# 09_SDIO_PERIPHERAL.net
KiCad netlist of a schematic drawn in Altium Designer
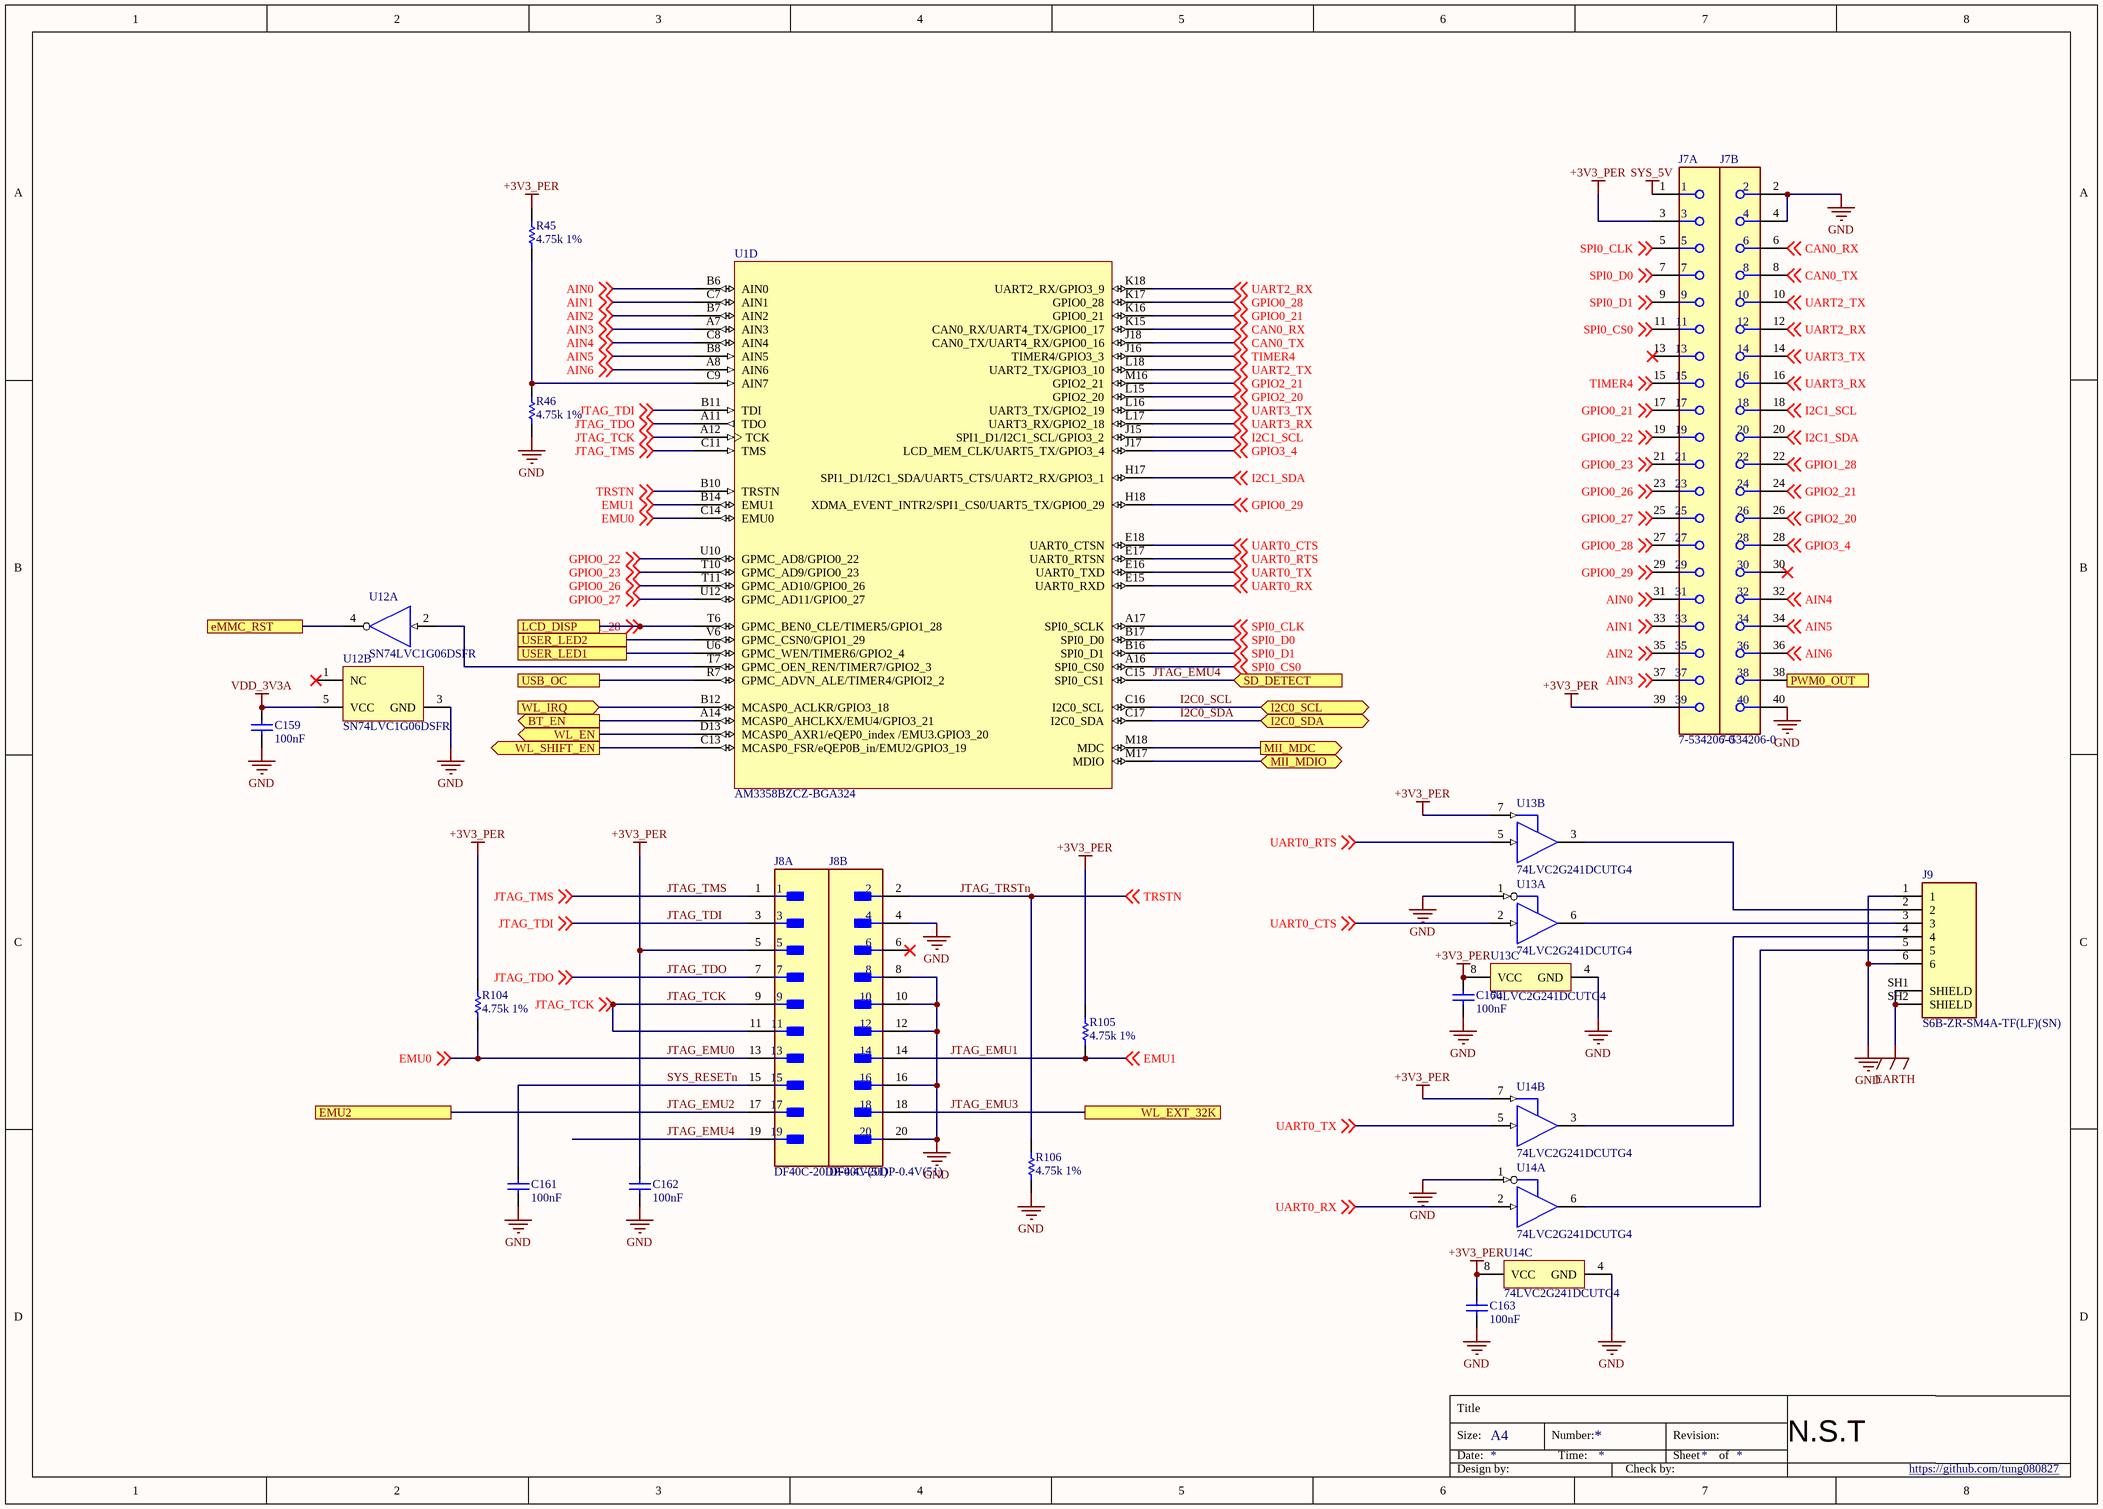
[diagram p0: 09. SDIO, PERIPHERAL.SchDoc]

(export (version "E")
  (design (tool "Eeschema 10.0.6"))
  (components
    (comp (ref "C159")
      (value "100nF")
      (footprint "CAPC1005X55X25LL05T10")
      (description "Chip Capacitor, 0.1 uF, +/- 10%, 16 V, -55 to 125 degC, 0402 (1005 Metric), RoHS, Tape and Reel")
      (fields (field (name "VOLTAGE") "16V") (field (name "TOLERANCE") "10%"))
      (libsource (lib "Altium Content Vault") (part "CAP-NP-2"))
    )
    (comp (ref "C160")
      (value "100nF")
      (footprint "CAPC1005X55X25LL05T10")
      (description "Chip Capacitor, 0.1 uF, +/- 10%, 16 V, -55 to 125 degC, 0402 (1005 Metric), RoHS, Tape and Reel")
      (fields (field (name "VOLTAGE") "16V") (field (name "TOLERANCE") "10%"))
      (libsource (lib "Altium Content Vault") (part "CAP-NP-2"))
    )
    (comp (ref "C161")
      (value "100nF")
      (footprint "CAPC1005X55X25LL05T10")
      (description "Chip Capacitor, 0.1 uF, +/- 10%, 16 V, -55 to 125 degC, 0402 (1005 Metric), RoHS, Tape and Reel")
      (fields (field (name "VOLTAGE") "16V") (field (name "TOLERANCE") "10%"))
      (libsource (lib "Altium Content Vault") (part "CAP-NP-2"))
    )
    (comp (ref "C162")
      (value "100nF")
      (footprint "CAPC1005X55X25LL05T10")
      (description "Chip Capacitor, 0.1 uF, +/- 10%, 16 V, -55 to 125 degC, 0402 (1005 Metric), RoHS, Tape and Reel")
      (fields (field (name "VOLTAGE") "16V") (field (name "TOLERANCE") "10%"))
      (libsource (lib "Altium Content Vault") (part "CAP-NP-2"))
    )
    (comp (ref "C163")
      (value "100nF")
      (footprint "CAPC1005X55X25LL05T10")
      (description "Chip Capacitor, 0.1 uF, +/- 10%, 16 V, -55 to 125 degC, 0402 (1005 Metric), RoHS, Tape and Reel")
      (fields (field (name "VOLTAGE") "16V") (field (name "TOLERANCE") "10%"))
      (libsource (lib "Altium Content Vault") (part "CAP-NP-2"))
    )
    (comp (ref "J7")
      (value "7-534206-0")
      (footprint "FP-7-534206-0-MFG")
      (description "CONN RCPT 40POS 0.1 GOLD PCB")
      (fields
        (field (name "MANUFACTURER") "TE Connectivity")
        (field (name "OCTOPART") "https://octopart.com/7-534206-0-te+connectivity-39516831")
      )
      (libsource (lib "Altium Content Vault") (part "7acf1c4a8db21028d11741a46a6ec78"))
    )
    (comp (ref "J8")
      (value "DF40C-20DP-0.4V(51)")
      (footprint "FP-DF40C-20DP-0_4V_51-MFG")
      (description "CONN PLUG 20POS SMD GOLD")
      (fields
        (field (name "MANUFACTURER") "Hirose")
        (field (name "OCTOPART") "https://octopart.com/df40c-20dp-0.4v%2851%29-hirose-11540400")
      )
      (libsource (lib "Altium Content Vault") (part "6de6f85b73b81876561c0123e7b9d68"))
    )
    (comp (ref "J9")
      (value "S6B-ZR-SM4A-TF(LF)(SN)")
      (footprint "JST_S6B-ZR-SM4A-TF")
      (description "Connector Header Surface Mount, Right Angle 6 position 0.059 _1.50mm_")
      (fields
        (field (name "MP") "S6B-ZR-SM4A-TF_LF__SN_")
        (field (name "DIGI-KEY_PART_NUMBER") "455-1610-1-ND")
      )
      (libsource (lib "SyTungNguyen") (part "S6B-ZR-SM4A-TF(LF)(SN)"))
    )
    (comp (ref "R45")
      (value "4.75k 1%")
      (footprint "RESC1005X40X25LL05T05")
      (fields (field (name "MANUFACTURER") "Vishay Dale") (field (name "PART NUMBER") "CRCW04024K75FKED"))
      (libsource (lib "AM3358_DEV_BOARD") (part "RES"))
    )
    (comp (ref "R46")
      (value "4.75k 1%")
      (footprint "RESC1005X40X25LL05T05")
      (fields (field (name "MANUFACTURER") "Vishay Dale") (field (name "PART NUMBER") "CRCW04024K75FKED"))
      (libsource (lib "AM3358_DEV_BOARD") (part "RES"))
    )
    (comp (ref "R104")
      (value "4.75k 1%")
      (footprint "RESC1005X40X25LL05T05")
      (fields (field (name "MANUFACTURER") "Vishay Dale") (field (name "PART NUMBER") "CRCW04024K75FKED"))
      (libsource (lib "AM3358_DEV_BOARD") (part "RES"))
    )
    (comp (ref "R105")
      (value "4.75k 1%")
      (footprint "RESC1005X40X25LL05T05")
      (fields (field (name "MANUFACTURER") "Vishay Dale") (field (name "PART NUMBER") "CRCW04024K75FKED"))
      (libsource (lib "AM3358_DEV_BOARD") (part "RES"))
    )
    (comp (ref "R106")
      (value "4.75k 1%")
      (footprint "RESC1005X40X25LL05T05")
      (fields (field (name "MANUFACTURER") "Vishay Dale") (field (name "PART NUMBER") "CRCW04024K75FKED"))
      (libsource (lib "AM3358_DEV_BOARD") (part "RES"))
    )
    (comp (ref "U1")
      (value "AM3358BZCZ-BGA324")
      (footprint "TI-ZCZ324")
      (libsource (lib "SyTungNguyen") (part "AM3358BZCZ100"))
    )
    (comp (ref "U12")
      (value "SN74LVC1G06DSFR")
      (footprint "DSF0006A_V")
      (description "Single Inverter Buffer/Driver With Open-Drain Output, DSF0006A, LARGE T&R")
      (fields
        (field (name "MANUFACTURER") "Texas Instruments")
        (field (name "GENERIC PART NUMBER") "SN74LVC1G06")
      )
      (libsource (lib "") (part "TI-SN74XXX1G06-5_1"))
    )
    (comp (ref "U13")
      (value "74LVC2G241DCUTG4")
      (footprint "DCU0008A_M")
      (description "Dual Buffer/Driver With 3-State Outputs, DCU0008A, SMALL T&R")
      (fields
        (field (name "MANUFACTURER") "Texas Instruments")
        (field (name "GENERIC PART NUMBER") "SN74LVC2G241")
      )
      (libsource (lib "Altium Content Vault") (part "TI-SN74XXX2G241-8"))
    )
    (comp (ref "U14")
      (value "74LVC2G241DCUTG4")
      (footprint "DCU0008A_M")
      (description "Dual Buffer/Driver With 3-State Outputs, DCU0008A, SMALL T&R")
      (fields
        (field (name "MANUFACTURER") "Texas Instruments")
        (field (name "GENERIC PART NUMBER") "SN74LVC2G241")
      )
      (libsource (lib "Altium Content Vault") (part "TI-SN74XXX2G241-8"))
    )
  )
  (nets
    (net (code "1") (name "+3V3_PER") (class "Default")
      (node (ref "C160") (pin "2") (pinfunction "2_2") (pintype "passive"))
      (node (ref "C162") (pin "2") (pinfunction "2_2") (pintype "passive"))
      (node (ref "C163") (pin "2") (pinfunction "2_2") (pintype "passive"))
      (node (ref "J7") (pin "3") (pinfunction "3_3") (pintype "passive"))
      (node (ref "J7") (pin "39") (pinfunction "39_39") (pintype "passive"))
      (node (ref "J8") (pin "5") (pinfunction "5_5") (pintype "passive"))
      (node (ref "R104") (pin "2") (pinfunction "2_2") (pintype "passive"))
      (node (ref "R105") (pin "2") (pinfunction "2_2") (pintype "passive"))
      (node (ref "R45") (pin "2") (pinfunction "2_2") (pintype "passive"))
      (node (ref "U13") (pin "7") (pinfunction "2OE_7") (pintype "input"))
      (node (ref "U13") (pin "8") (pinfunction "VCC_8") (pintype "power_in"))
      (node (ref "U14") (pin "7") (pinfunction "2OE_7") (pintype "input"))
      (node (ref "U14") (pin "8") (pinfunction "VCC_8") (pintype "power_in"))
    )
    (net (code "2") (name "/BT_EN") (class "Default")
      (node (ref "U1") (pin "A14") (pinfunction "MCASP0_AHCLKX/EMU4/GPIO3_21_A14") (pintype "bidirectional"))
    )
    (net (code "3") (name "/I2C0_SCL") (class "Default")
      (node (ref "U1") (pin "C16") (pinfunction "I2C0_SCL_C16") (pintype "bidirectional"))
    )
    (net (code "4") (name "/I2C0_SDA") (class "Default")
      (node (ref "U1") (pin "C17") (pinfunction "I2C0_SDA_C17") (pintype "bidirectional"))
    )
    (net (code "5") (name "/JTAG_EMU2") (class "Default")
      (node (ref "J8") (pin "17") (pinfunction "17_17") (pintype "passive"))
    )
    (net (code "6") (name "/JTAG_EMU3") (class "Default")
      (node (ref "J8") (pin "18") (pinfunction "18_18") (pintype "passive"))
    )
    (net (code "7") (name "/JTAG_EMU4") (class "Default")
      (node (ref "J8") (pin "19") (pinfunction "19_19") (pintype "passive"))
      (node (ref "U1") (pin "C15") (pinfunction "SPI0_CS1_C15") (pintype "bidirectional"))
    )
    (net (code "8") (name "/MII_MDC") (class "Default")
      (node (ref "U1") (pin "M18") (pinfunction "MDC_M18") (pintype "bidirectional"))
    )
    (net (code "9") (name "/MII_MDIO") (class "Default")
      (node (ref "U1") (pin "M17") (pinfunction "MDIO_M17") (pintype "bidirectional"))
    )
    (net (code "10") (name "/PWM0_OUT") (class "Default")
      (node (ref "J7") (pin "38") (pinfunction "38_38") (pintype "passive"))
    )
    (net (code "11") (name "/SYS_RESETn") (class "Default")
      (node (ref "C161") (pin "2") (pinfunction "2_2") (pintype "passive"))
      (node (ref "J8") (pin "15") (pinfunction "15_15") (pintype "passive"))
    )
    (net (code "12") (name "/USB_OC") (class "Default")
      (node (ref "U1") (pin "R7") (pinfunction "GPMC_ADVN_ALE/TIMER4/GPIOI2_2_R7") (pintype "bidirectional"))
    )
    (net (code "13") (name "/USER_LED1") (class "Default")
      (node (ref "U1") (pin "U6") (pinfunction "GPMC_WEN/TIMER6/GPIO2_4_U6") (pintype "bidirectional"))
    )
    (net (code "14") (name "/USER_LED2") (class "Default")
      (node (ref "U1") (pin "V6") (pinfunction "GPMC_CSN0/GPIO1_29_V6") (pintype "bidirectional"))
    )
    (net (code "15") (name "/WL_EN") (class "Default")
      (node (ref "U1") (pin "D13") (pinfunction "MCASP0_AXR1/eQEP0_index_/EMU3.GPIO3_20_D13") (pintype "bidirectional"))
    )
    (net (code "16") (name "/WL_IRQ") (class "Default")
      (node (ref "U1") (pin "B12") (pinfunction "MCASP0_ACLKR/GPIO3_18_B12") (pintype "bidirectional"))
    )
    (net (code "17") (name "/WL_SHIFT_EN") (class "Default")
      (node (ref "U1") (pin "C13") (pinfunction "MCASP0_FSR/eQEP0B_in/EMU2/GPIO3_19_C13") (pintype "bidirectional"))
    )
    (net (code "18") (name "/eMMC_RST") (class "Default")
      (node (ref "U12") (pin "4") (pinfunction "Y_4") (pintype "open_collector"))
    )
    (net (code "19") (name "AIN0") (class "Default")
      (node (ref "J7") (pin "31") (pinfunction "31_31") (pintype "passive"))
      (node (ref "U1") (pin "B6") (pinfunction "AIN0_B6") (pintype "bidirectional"))
    )
    (net (code "20") (name "AIN1") (class "Default")
      (node (ref "J7") (pin "33") (pinfunction "33_33") (pintype "passive"))
      (node (ref "U1") (pin "C7") (pinfunction "AIN1_C7") (pintype "bidirectional"))
    )
    (net (code "21") (name "AIN2") (class "Default")
      (node (ref "J7") (pin "35") (pinfunction "35_35") (pintype "passive"))
      (node (ref "U1") (pin "B7") (pinfunction "AIN2_B7") (pintype "bidirectional"))
    )
    (net (code "22") (name "AIN3") (class "Default")
      (node (ref "J7") (pin "37") (pinfunction "37_37") (pintype "passive"))
      (node (ref "U1") (pin "A7") (pinfunction "AIN3_A7") (pintype "bidirectional"))
    )
    (net (code "23") (name "AIN4") (class "Default")
      (node (ref "J7") (pin "32") (pinfunction "32_32") (pintype "passive"))
      (node (ref "U1") (pin "C8") (pinfunction "AIN4_C8") (pintype "bidirectional"))
    )
    (net (code "24") (name "AIN5") (class "Default")
      (node (ref "J7") (pin "34") (pinfunction "34_34") (pintype "passive"))
      (node (ref "U1") (pin "B8") (pinfunction "AIN5_B8") (pintype "input"))
    )
    (net (code "25") (name "AIN6") (class "Default")
      (node (ref "J7") (pin "36") (pinfunction "36_36") (pintype "passive"))
      (node (ref "U1") (pin "A8") (pinfunction "AIN6_A8") (pintype "input"))
    )
    (net (code "26") (name "CAN0_RX") (class "Default")
      (node (ref "J7") (pin "6") (pinfunction "6_6") (pintype "passive"))
      (node (ref "U1") (pin "K15") (pinfunction "CAN0_RX/UART4_TX/GPIO0_17_K15") (pintype "bidirectional"))
    )
    (net (code "27") (name "CAN0_TX") (class "Default")
      (node (ref "J7") (pin "8") (pinfunction "8_8") (pintype "passive"))
      (node (ref "U1") (pin "J18") (pinfunction "CAN0_TX/UART4_RX/GPIO0_16_J18") (pintype "bidirectional"))
    )
    (net (code "28") (name "EARTH") (class "Default")
      (node (ref "J9") (pin "SH1") (pinfunction "SHIELD_SH1") (pintype "passive"))
      (node (ref "J9") (pin "SH2") (pinfunction "SHIELD_SH2") (pintype "passive"))
    )
    (net (code "29") (name "EMU0") (class "Default")
      (node (ref "J8") (pin "13") (pinfunction "13_13") (pintype "passive"))
      (node (ref "R104") (pin "1") (pinfunction "1_1") (pintype "passive"))
      (node (ref "U1") (pin "C14") (pinfunction "EMU0_C14") (pintype "bidirectional"))
    )
    (net (code "30") (name "EMU1") (class "Default")
      (node (ref "J8") (pin "14") (pinfunction "14_14") (pintype "passive"))
      (node (ref "R105") (pin "1") (pinfunction "1_1") (pintype "passive"))
      (node (ref "U1") (pin "B14") (pinfunction "EMU1_B14") (pintype "bidirectional"))
    )
    (net (code "31") (name "GND") (class "Default")
      (node (ref "C159") (pin "1") (pinfunction "1_1") (pintype "passive"))
      (node (ref "C160") (pin "1") (pinfunction "1_1") (pintype "passive"))
      (node (ref "C161") (pin "1") (pinfunction "1_1") (pintype "passive"))
      (node (ref "C162") (pin "1") (pinfunction "1_1") (pintype "passive"))
      (node (ref "C163") (pin "1") (pinfunction "1_1") (pintype "passive"))
      (node (ref "J7") (pin "2") (pinfunction "2_2") (pintype "passive"))
      (node (ref "J7") (pin "4") (pinfunction "4_4") (pintype "passive"))
      (node (ref "J7") (pin "40") (pinfunction "40_40") (pintype "passive"))
      (node (ref "J8") (pin "10") (pinfunction "10_10") (pintype "passive"))
      (node (ref "J8") (pin "12") (pinfunction "12_12") (pintype "passive"))
      (node (ref "J8") (pin "16") (pinfunction "16_16") (pintype "passive"))
      (node (ref "J8") (pin "20") (pinfunction "20_20") (pintype "passive"))
      (node (ref "J8") (pin "4") (pinfunction "4_4") (pintype "passive"))
      (node (ref "J8") (pin "8") (pinfunction "8_8") (pintype "passive"))
      (node (ref "J9") (pin "1") (pinfunction "1_1") (pintype "passive"))
      (node (ref "J9") (pin "6") (pinfunction "6_6") (pintype "passive"))
      (node (ref "R106") (pin "1") (pinfunction "1_1") (pintype "passive"))
      (node (ref "R46") (pin "1") (pinfunction "1_1") (pintype "passive"))
      (node (ref "U12") (pin "3") (pinfunction "GND_3") (pintype "power_in"))
      (node (ref "U13") (pin "1") (pinfunction "1~{OE}_1") (pintype "input"))
      (node (ref "U13") (pin "4") (pinfunction "GND_4") (pintype "power_in"))
      (node (ref "U14") (pin "1") (pinfunction "1~{OE}_1") (pintype "input"))
      (node (ref "U14") (pin "4") (pinfunction "GND_4") (pintype "power_in"))
    )
    (net (code "32") (name "GPIO0_21") (class "Default")
      (node (ref "J7") (pin "17") (pinfunction "17_17") (pintype "passive"))
      (node (ref "U1") (pin "K16") (pinfunction "GPIO0_21_K16") (pintype "bidirectional"))
    )
    (net (code "33") (name "GPIO0_22") (class "Default")
      (node (ref "J7") (pin "19") (pinfunction "19_19") (pintype "passive"))
      (node (ref "U1") (pin "U10") (pinfunction "GPMC_AD8/GPIO0_22_U10") (pintype "bidirectional"))
    )
    (net (code "34") (name "GPIO0_23") (class "Default")
      (node (ref "J7") (pin "21") (pinfunction "21_21") (pintype "passive"))
      (node (ref "U1") (pin "T10") (pinfunction "GPMC_AD9/GPIO0_23_T10") (pintype "bidirectional"))
    )
    (net (code "35") (name "GPIO0_26") (class "Default")
      (node (ref "J7") (pin "23") (pinfunction "23_23") (pintype "passive"))
      (node (ref "U1") (pin "T11") (pinfunction "GPMC_AD10/GPIO0_26_T11") (pintype "bidirectional"))
    )
    (net (code "36") (name "GPIO0_27") (class "Default")
      (node (ref "J7") (pin "25") (pinfunction "25_25") (pintype "passive"))
      (node (ref "U1") (pin "U12") (pinfunction "GPMC_AD11/GPIO0_27_U12") (pintype "bidirectional"))
    )
    (net (code "37") (name "GPIO0_28") (class "Default")
      (node (ref "J7") (pin "27") (pinfunction "27_27") (pintype "passive"))
      (node (ref "U1") (pin "K17") (pinfunction "GPIO0_28_K17") (pintype "bidirectional"))
    )
    (net (code "38") (name "GPIO0_29") (class "Default")
      (node (ref "J7") (pin "29") (pinfunction "29_29") (pintype "passive"))
      (node (ref "U1") (pin "H18") (pinfunction "XDMA_EVENT_INTR2/SPI1_CS0/UART5_TX/GPIO0_29_H18") (pintype "bidirectional"))
    )
    (net (code "39") (name "GPIO1_28") (class "Default")
      (node (ref "J7") (pin "22") (pinfunction "22_22") (pintype "passive"))
      (node (ref "U1") (pin "T6") (pinfunction "GPMC_BEN0_CLE/TIMER5/GPIO1_28_T6") (pintype "bidirectional"))
    )
    (net (code "40") (name "GPIO2_20") (class "Default")
      (node (ref "J7") (pin "26") (pinfunction "26_26") (pintype "passive"))
      (node (ref "U1") (pin "L15") (pinfunction "GPIO2_20_L15") (pintype "bidirectional"))
    )
    (net (code "41") (name "GPIO2_21") (class "Default")
      (node (ref "J7") (pin "24") (pinfunction "24_24") (pintype "passive"))
      (node (ref "U1") (pin "M16") (pinfunction "GPIO2_21_M16") (pintype "bidirectional"))
    )
    (net (code "42") (name "GPIO3_4") (class "Default")
      (node (ref "J7") (pin "28") (pinfunction "28_28") (pintype "passive"))
      (node (ref "U1") (pin "J17") (pinfunction "LCD_MEM_CLK/UART5_TX/GPIO3_4_J17") (pintype "bidirectional"))
    )
    (net (code "43") (name "I2C1_SCL") (class "Default")
      (node (ref "J7") (pin "18") (pinfunction "18_18") (pintype "passive"))
      (node (ref "U1") (pin "J15") (pinfunction "SPI1_D1/I2C1_SCL/GPIO3_2_J15") (pintype "bidirectional"))
    )
    (net (code "44") (name "I2C1_SDA") (class "Default")
      (node (ref "J7") (pin "20") (pinfunction "20_20") (pintype "passive"))
      (node (ref "U1") (pin "H17") (pinfunction "SPI1_D1/I2C1_SDA/UART5_CTS/UART2_RX/GPIO3_1_H17") (pintype "bidirectional"))
    )
    (net (code "45") (name "JTAG_TCK") (class "Default")
      (node (ref "J8") (pin "11") (pinfunction "11_11") (pintype "passive"))
      (node (ref "J8") (pin "9") (pinfunction "9_9") (pintype "passive"))
      (node (ref "U1") (pin "A12") (pinfunction "TCK_A12") (pintype "input"))
    )
    (net (code "46") (name "JTAG_TDI") (class "Default")
      (node (ref "J8") (pin "3") (pinfunction "3_3") (pintype "passive"))
      (node (ref "U1") (pin "B11") (pinfunction "TDI_B11") (pintype "input"))
    )
    (net (code "47") (name "JTAG_TDO") (class "Default")
      (node (ref "J8") (pin "7") (pinfunction "7_7") (pintype "passive"))
      (node (ref "U1") (pin "A11") (pinfunction "TDO_A11") (pintype "output"))
    )
    (net (code "48") (name "JTAG_TMS") (class "Default")
      (node (ref "J8") (pin "1") (pinfunction "1_1") (pintype "passive"))
      (node (ref "U1") (pin "C11") (pinfunction "TMS_C11") (pintype "input"))
    )
    (net (code "49") (name "Net-(U1D-AIN7)") (class "Default")
      (node (ref "R45") (pin "1") (pinfunction "1_1") (pintype "passive"))
      (node (ref "R46") (pin "2") (pinfunction "2_2") (pintype "passive"))
      (node (ref "U1") (pin "C9") (pinfunction "AIN7_C9") (pintype "input"))
    )
    (net (code "50") (name "Net-(U12A-A)") (class "Default")
      (node (ref "U1") (pin "T7") (pinfunction "GPMC_OEN_REN/TIMER7/GPIO2_3_T7") (pintype "bidirectional"))
      (node (ref "U12") (pin "2") (pinfunction "A_2") (pintype "input"))
    )
    (net (code "51") (name "Net-(U13A-1Y)") (class "Default")
      (node (ref "J9") (pin "3") (pinfunction "3_3") (pintype "passive"))
      (node (ref "U13") (pin "6") (pinfunction "1Y_6") (pintype "tri_state"))
    )
    (net (code "52") (name "Net-(U13B-2Y)") (class "Default")
      (node (ref "J9") (pin "2") (pinfunction "2_2") (pintype "passive"))
      (node (ref "U13") (pin "3") (pinfunction "2Y_3") (pintype "tri_state"))
    )
    (net (code "53") (name "Net-(U14A-1Y)") (class "Default")
      (node (ref "J9") (pin "5") (pinfunction "5_5") (pintype "passive"))
      (node (ref "U14") (pin "6") (pinfunction "1Y_6") (pintype "tri_state"))
    )
    (net (code "54") (name "Net-(U14B-2Y)") (class "Default")
      (node (ref "J9") (pin "4") (pinfunction "4_4") (pintype "passive"))
      (node (ref "U14") (pin "3") (pinfunction "2Y_3") (pintype "tri_state"))
    )
    (net (code "55") (name "SPI0_CLK") (class "Default")
      (node (ref "J7") (pin "5") (pinfunction "5_5") (pintype "passive"))
      (node (ref "U1") (pin "A17") (pinfunction "SPI0_SCLK_A17") (pintype "bidirectional"))
    )
    (net (code "56") (name "SPI0_CS0") (class "Default")
      (node (ref "J7") (pin "11") (pinfunction "11_11") (pintype "passive"))
      (node (ref "U1") (pin "A16") (pinfunction "SPI0_CS0_A16") (pintype "bidirectional"))
    )
    (net (code "57") (name "SPI0_D0") (class "Default")
      (node (ref "J7") (pin "7") (pinfunction "7_7") (pintype "passive"))
      (node (ref "U1") (pin "B17") (pinfunction "SPI0_D0_B17") (pintype "bidirectional"))
    )
    (net (code "58") (name "SPI0_D1") (class "Default")
      (node (ref "J7") (pin "9") (pinfunction "9_9") (pintype "passive"))
      (node (ref "U1") (pin "B16") (pinfunction "SPI0_D1_B16") (pintype "bidirectional"))
    )
    (net (code "59") (name "SYS_5V") (class "Default")
      (node (ref "J7") (pin "1") (pinfunction "1_1") (pintype "passive"))
    )
    (net (code "60") (name "TIMER4") (class "Default")
      (node (ref "J7") (pin "15") (pinfunction "15_15") (pintype "passive"))
      (node (ref "U1") (pin "J16") (pinfunction "TIMER4/GPIO3_3_J16") (pintype "bidirectional"))
    )
    (net (code "61") (name "TRSTN") (class "Default")
      (node (ref "J8") (pin "2") (pinfunction "2_2") (pintype "passive"))
      (node (ref "R106") (pin "2") (pinfunction "2_2") (pintype "passive"))
      (node (ref "U1") (pin "B10") (pinfunction "TRSTN_B10") (pintype "input"))
    )
    (net (code "62") (name "UART0_CTS") (class "Default")
      (node (ref "U1") (pin "E18") (pinfunction "UART0_CTSN_E18") (pintype "bidirectional"))
      (node (ref "U13") (pin "2") (pinfunction "1A_2") (pintype "input"))
    )
    (net (code "63") (name "UART0_RTS") (class "Default")
      (node (ref "U1") (pin "E17") (pinfunction "UART0_RTSN_E17") (pintype "bidirectional"))
      (node (ref "U13") (pin "5") (pinfunction "2A_5") (pintype "input"))
    )
    (net (code "64") (name "UART0_RX") (class "Default")
      (node (ref "U1") (pin "E15") (pinfunction "UART0_RXD_E15") (pintype "bidirectional"))
      (node (ref "U14") (pin "2") (pinfunction "1A_2") (pintype "input"))
    )
    (net (code "65") (name "UART0_TX") (class "Default")
      (node (ref "U1") (pin "E16") (pinfunction "UART0_TXD_E16") (pintype "bidirectional"))
      (node (ref "U14") (pin "5") (pinfunction "2A_5") (pintype "input"))
    )
    (net (code "66") (name "UART2_RX") (class "Default")
      (node (ref "J7") (pin "12") (pinfunction "12_12") (pintype "passive"))
      (node (ref "U1") (pin "K18") (pinfunction "UART2_RX/GPIO3_9_K18") (pintype "bidirectional"))
    )
    (net (code "67") (name "UART2_TX") (class "Default")
      (node (ref "J7") (pin "10") (pinfunction "10_10") (pintype "passive"))
      (node (ref "U1") (pin "L18") (pinfunction "UART2_TX/GPIO3_10_L18") (pintype "bidirectional"))
    )
    (net (code "68") (name "UART3_RX") (class "Default")
      (node (ref "J7") (pin "16") (pinfunction "16_16") (pintype "passive"))
      (node (ref "U1") (pin "L17") (pinfunction "UART3_RX/GPIO2_18_L17") (pintype "bidirectional"))
    )
    (net (code "69") (name "UART3_TX") (class "Default")
      (node (ref "J7") (pin "14") (pinfunction "14_14") (pintype "passive"))
      (node (ref "U1") (pin "L16") (pinfunction "UART3_TX/GPIO2_19_L16") (pintype "bidirectional"))
    )
    (net (code "70") (name "VDD_3V3A") (class "Default")
      (node (ref "C159") (pin "2") (pinfunction "2_2") (pintype "passive"))
      (node (ref "U12") (pin "5") (pinfunction "VCC_5") (pintype "power_in"))
    )
    (net (code "71") (name "unconnected-(J7-Pad13)") (class "Default")
      (node (ref "J7") (pin "13") (pinfunction "13_13") (pintype "passive+no_connect"))
    )
    (net (code "72") (name "unconnected-(J7-Pad30)") (class "Default")
      (node (ref "J7") (pin "30") (pinfunction "30_30") (pintype "passive+no_connect"))
    )
    (net (code "73") (name "unconnected-(J8-Pad6)") (class "Default")
      (node (ref "J8") (pin "6") (pinfunction "6_6") (pintype "passive+no_connect"))
    )
    (net (code "74") (name "unconnected-(U12B-NC-Pad1)") (class "Default")
      (node (ref "U12") (pin "1") (pinfunction "NC_1") (pintype "passive+no_connect"))
    )
  )
)
